# stm32f3-shield.net
KiCad netlist of a schematic drawn in EAGLE
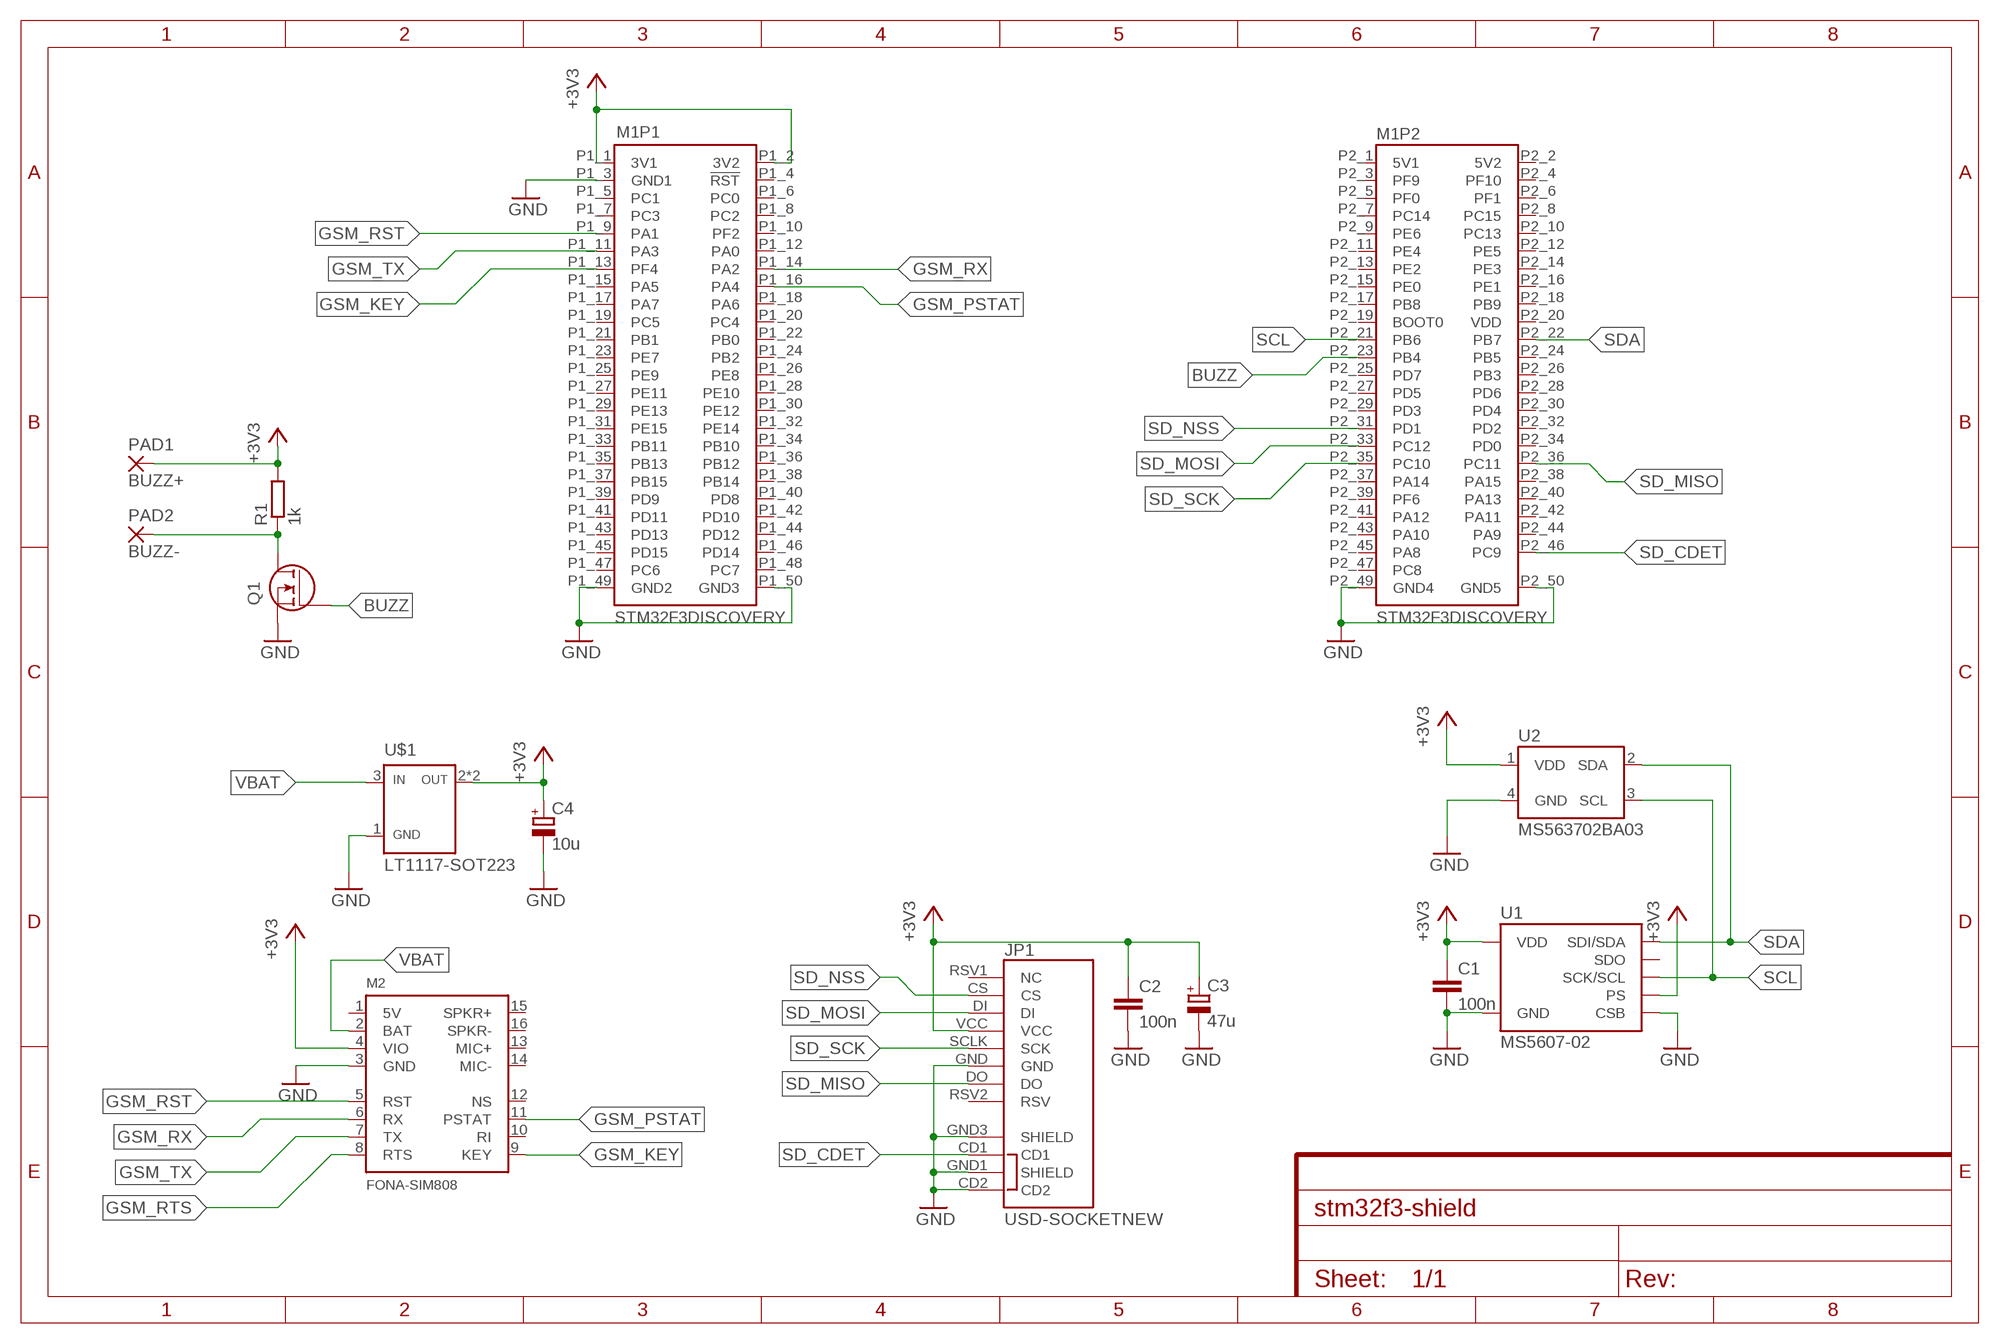
[diagram p0: schematic, sheet 1]

(export (version "E")
  (design (tool "Eeschema 10.0.6"))
  (components
    (comp (ref "C1")
      (value "100n")
      (footprint "eagle-import:C0805K")
      (libsource (lib "eagle-import") (part "C-EUC0805K"))
    )
    (comp (ref "C2")
      (value "100n")
      (footprint "eagle-import:C0805K")
      (libsource (lib "eagle-import") (part "C-EUC0805K"))
    )
    (comp (ref "C3")
      (value "47u")
      (footprint "eagle-import:SMC_B")
      (libsource (lib "eagle-import") (part "CPOL-EUSMCB"))
    )
    (comp (ref "C4")
      (value "10u")
      (footprint "eagle-import:SMC_B")
      (libsource (lib "eagle-import") (part "CPOL-EUSMCB"))
    )
    (comp (ref "JP1")
      (value "USD-SOCKETNEW")
      (footprint "eagle-import:MICRO-SD-SOCKET-PP")
      (libsource (lib "eagle-import") (part "USD-SOCKETNEW"))
    )
    (comp (ref "M1")
      (value "STM32F3DISCOVERY")
      (footprint "eagle-import:STM32F3DISCOVERY")
      (libsource (lib "eagle-import") (part "STM32F3DISCOVERY"))
    )
    (comp (ref "M2")
      (value "FONA-SIM808")
      (footprint "eagle-import:FONA-SIM808")
      (libsource (lib "eagle-import") (part "FONA-SIM808"))
    )
    (comp (ref "PAD1")
      (value "BUZZ+")
      (footprint "eagle-import:2,54_0,8")
      (libsource (lib "eagle-import") (part "2,54/0,8"))
    )
    (comp (ref "PAD2")
      (value "BUZZ-")
      (footprint "eagle-import:2,54_0,8")
      (libsource (lib "eagle-import") (part "2,54/0,8"))
    )
    (comp (ref "Q1")
      (value "MOSFET-N-SOT23-3")
      (footprint "eagle-import:SOT23-3")
      (libsource (lib "eagle-import") (part "MOSFET-N-SOT23-3"))
    )
    (comp (ref "R1")
      (value "1k")
      (footprint "eagle-import:R0603")
      (libsource (lib "eagle-import") (part "R-EU_R0603"))
    )
    (comp (ref "U$1")
      (value "LT1117-SOT223")
      (footprint "eagle-import:SOT223")
      (libsource (lib "eagle-import") (part "LT1117-SOT223"))
    )
    (comp (ref "U1")
      (value "MS5607-02")
      (footprint "eagle-import:LGA8")
      (libsource (lib "eagle-import") (part "MS5607-02"))
    )
    (comp (ref "U2")
      (value "MS563702BA03")
      (footprint "eagle-import:MS5637")
      (libsource (lib "eagle-import") (part "MS563702BA03"))
    )
  )
  (nets
    (net (code "1") (name "+3V3") (class "Default")
      (node (ref "C1") (pin "1") (pinfunction "1_1") (pintype "passive"))
      (node (ref "C2") (pin "1") (pinfunction "1_1") (pintype "passive"))
      (node (ref "C3") (pin "+") (pinfunction "+_+") (pintype "passive"))
      (node (ref "C4") (pin "+") (pinfunction "+_+") (pintype "passive"))
      (node (ref "JP1") (pin "VCC") (pinfunction "VCC_VCC") (pintype "bidirectional"))
      (node (ref "M1") (pin "P1_1") (pinfunction "3V1_P1_1") (pintype "bidirectional"))
      (node (ref "M1") (pin "P1_2") (pinfunction "3V2_P1_2") (pintype "bidirectional"))
      (node (ref "M2") (pin "4") (pinfunction "VIO_4") (pintype "bidirectional"))
      (node (ref "PAD1") (pin "1") (pinfunction "P_1") (pintype "passive"))
      (node (ref "R1") (pin "2") (pinfunction "2_2") (pintype "passive"))
      (node (ref "U$1") (pin "2") (pinfunction "OUT_2") (pintype "bidirectional"))
      (node (ref "U$1") (pin "4") (pinfunction "OUT_4") (pintype "bidirectional"))
      (node (ref "U1") (pin "1") (pinfunction "VDD_1") (pintype "power_in"))
      (node (ref "U1") (pin "2") (pinfunction "PS_2") (pintype "input"))
      (node (ref "U2") (pin "1") (pinfunction "VDD_1") (pintype "bidirectional"))
    )
    (net (code "2") (name "BUZZ") (class "Default")
      (node (ref "M1") (pin "P2_23") (pinfunction "PB4_P2_23") (pintype "bidirectional"))
      (node (ref "Q1") (pin "1") (pinfunction "G_1") (pintype "passive"))
    )
    (net (code "3") (name "GND") (class "Default")
      (node (ref "C1") (pin "2") (pinfunction "2_2") (pintype "passive"))
      (node (ref "C2") (pin "2") (pinfunction "2_2") (pintype "passive"))
      (node (ref "C3") (pin "-") (pinfunction "-_-") (pintype "passive"))
      (node (ref "C4") (pin "-") (pinfunction "-_-") (pintype "passive"))
      (node (ref "JP1") (pin "CD2") (pinfunction "CD2_CD2") (pintype "bidirectional"))
      (node (ref "JP1") (pin "GND") (pinfunction "GND_GND") (pintype "bidirectional"))
      (node (ref "JP1") (pin "GND1") (pinfunction "SHIELD_GND1") (pintype "bidirectional"))
      (node (ref "JP1") (pin "GND3") (pinfunction "SHIELD_GND3") (pintype "bidirectional"))
      (node (ref "M1") (pin "P1_3") (pinfunction "GND1_P1_3") (pintype "bidirectional"))
      (node (ref "M1") (pin "P1_49") (pinfunction "GND2_P1_49") (pintype "bidirectional"))
      (node (ref "M1") (pin "P1_50") (pinfunction "GND3_P1_50") (pintype "bidirectional"))
      (node (ref "M1") (pin "P2_49") (pinfunction "GND4_P2_49") (pintype "bidirectional"))
      (node (ref "M1") (pin "P2_50") (pinfunction "GND5_P2_50") (pintype "bidirectional"))
      (node (ref "M2") (pin "3") (pinfunction "GND_3") (pintype "bidirectional"))
      (node (ref "Q1") (pin "2") (pinfunction "S_2") (pintype "passive"))
      (node (ref "U$1") (pin "1") (pinfunction "GND_1") (pintype "bidirectional"))
      (node (ref "U1") (pin "3") (pinfunction "GND_3") (pintype "power_in"))
      (node (ref "U1") (pin "4") (pinfunction "CSB_4") (pintype "input"))
      (node (ref "U1") (pin "5") (pinfunction "CSB_5") (pintype "input"))
      (node (ref "U2") (pin "4") (pinfunction "GND_4") (pintype "bidirectional"))
    )
    (net (code "4") (name "GSM_KEY") (class "Default")
      (node (ref "M1") (pin "P1_13") (pinfunction "PF4_P1_13") (pintype "bidirectional"))
      (node (ref "M2") (pin "9") (pinfunction "KEY_9") (pintype "bidirectional"))
    )
    (net (code "5") (name "GSM_PSTAT") (class "Default")
      (node (ref "M1") (pin "P1_16") (pinfunction "PA4_P1_16") (pintype "bidirectional"))
      (node (ref "M2") (pin "11") (pinfunction "PSTAT_11") (pintype "bidirectional"))
    )
    (net (code "6") (name "GSM_RST") (class "Default")
      (node (ref "M1") (pin "P1_9") (pinfunction "PA1_P1_9") (pintype "bidirectional"))
      (node (ref "M2") (pin "5") (pinfunction "RST_5") (pintype "bidirectional"))
    )
    (net (code "7") (name "GSM_RTS") (class "Default")
      (node (ref "M2") (pin "8") (pinfunction "RTS_8") (pintype "bidirectional"))
    )
    (net (code "8") (name "GSM_RX") (class "Default")
      (node (ref "M1") (pin "P1_14") (pinfunction "PA2_P1_14") (pintype "bidirectional"))
      (node (ref "M2") (pin "6") (pinfunction "RX_6") (pintype "bidirectional"))
    )
    (net (code "9") (name "GSM_TX") (class "Default")
      (node (ref "M1") (pin "P1_11") (pinfunction "PA3_P1_11") (pintype "bidirectional"))
      (node (ref "M2") (pin "7") (pinfunction "TX_7") (pintype "bidirectional"))
    )
    (net (code "10") (name "Net-(PAD2-P)") (class "Default")
      (node (ref "PAD2") (pin "1") (pinfunction "P_1") (pintype "passive"))
      (node (ref "Q1") (pin "3") (pinfunction "D_3") (pintype "passive"))
      (node (ref "R1") (pin "1") (pinfunction "1_1") (pintype "passive"))
    )
    (net (code "11") (name "SCL") (class "Default")
      (node (ref "M1") (pin "P2_21") (pinfunction "PB6_P2_21") (pintype "bidirectional"))
      (node (ref "U1") (pin "8") (pinfunction "SCK/SCL_8") (pintype "input"))
      (node (ref "U2") (pin "3") (pinfunction "SCL_3") (pintype "bidirectional"))
    )
    (net (code "12") (name "SDA") (class "Default")
      (node (ref "M1") (pin "P2_22") (pinfunction "PB7_P2_22") (pintype "bidirectional"))
      (node (ref "U1") (pin "7") (pinfunction "SDI/SDA_7") (pintype "bidirectional"))
      (node (ref "U2") (pin "2") (pinfunction "SDA_2") (pintype "bidirectional"))
    )
    (net (code "13") (name "SD_CDET") (class "Default")
      (node (ref "JP1") (pin "CD1") (pinfunction "CD1_CD1") (pintype "bidirectional"))
      (node (ref "M1") (pin "P2_46") (pinfunction "PC9_P2_46") (pintype "bidirectional"))
    )
    (net (code "14") (name "SD_MISO") (class "Default")
      (node (ref "JP1") (pin "DO") (pinfunction "DO_DO") (pintype "bidirectional"))
      (node (ref "M1") (pin "P2_36") (pinfunction "PC11_P2_36") (pintype "bidirectional"))
    )
    (net (code "15") (name "SD_MOSI") (class "Default")
      (node (ref "JP1") (pin "DI") (pinfunction "DI_DI") (pintype "bidirectional"))
      (node (ref "M1") (pin "P2_33") (pinfunction "PC12_P2_33") (pintype "bidirectional"))
    )
    (net (code "16") (name "SD_NSS") (class "Default")
      (node (ref "JP1") (pin "CS") (pinfunction "CS_CS") (pintype "bidirectional"))
      (node (ref "M1") (pin "P2_31") (pinfunction "PD1_P2_31") (pintype "bidirectional"))
    )
    (net (code "17") (name "SD_SCK") (class "Default")
      (node (ref "JP1") (pin "SCLK") (pinfunction "SCK_SCLK") (pintype "bidirectional"))
      (node (ref "M1") (pin "P2_35") (pinfunction "PC10_P2_35") (pintype "bidirectional"))
    )
    (net (code "18") (name "VBAT") (class "Default")
      (node (ref "M2") (pin "2") (pinfunction "BAT_2") (pintype "bidirectional"))
      (node (ref "U$1") (pin "3") (pinfunction "IN_3") (pintype "bidirectional"))
    )
    (net (code "19") (name "unconnected-(JP1-NC-PadRSV1)") (class "Default")
      (node (ref "JP1") (pin "RSV1") (pinfunction "NC_RSV1") (pintype "bidirectional"))
    )
    (net (code "20") (name "unconnected-(JP1-RSV-PadRSV2)") (class "Default")
      (node (ref "JP1") (pin "RSV2") (pinfunction "RSV_RSV2") (pintype "bidirectional"))
    )
    (net (code "21") (name "unconnected-(M1A-PA0-PadP1_12)") (class "Default")
      (node (ref "M1") (pin "P1_12") (pinfunction "PA0_P1_12") (pintype "bidirectional"))
    )
    (net (code "22") (name "unconnected-(M1A-PA5-PadP1_15)") (class "Default")
      (node (ref "M1") (pin "P1_15") (pinfunction "PA5_P1_15") (pintype "bidirectional"))
    )
    (net (code "23") (name "unconnected-(M1A-PA6-PadP1_18)") (class "Default")
      (node (ref "M1") (pin "P1_18") (pinfunction "PA6_P1_18") (pintype "bidirectional"))
    )
    (net (code "24") (name "unconnected-(M1A-PA7-PadP1_17)") (class "Default")
      (node (ref "M1") (pin "P1_17") (pinfunction "PA7_P1_17") (pintype "bidirectional"))
    )
    (net (code "25") (name "unconnected-(M1A-PB0-PadP1_22)") (class "Default")
      (node (ref "M1") (pin "P1_22") (pinfunction "PB0_P1_22") (pintype "bidirectional"))
    )
    (net (code "26") (name "unconnected-(M1A-PB1-PadP1_21)") (class "Default")
      (node (ref "M1") (pin "P1_21") (pinfunction "PB1_P1_21") (pintype "bidirectional"))
    )
    (net (code "27") (name "unconnected-(M1A-PB2-PadP1_24)") (class "Default")
      (node (ref "M1") (pin "P1_24") (pinfunction "PB2_P1_24") (pintype "bidirectional"))
    )
    (net (code "28") (name "unconnected-(M1A-PB10-PadP1_34)") (class "Default")
      (node (ref "M1") (pin "P1_34") (pinfunction "PB10_P1_34") (pintype "bidirectional"))
    )
    (net (code "29") (name "unconnected-(M1A-PB11-PadP1_33)") (class "Default")
      (node (ref "M1") (pin "P1_33") (pinfunction "PB11_P1_33") (pintype "bidirectional"))
    )
    (net (code "30") (name "unconnected-(M1A-PB12-PadP1_36)") (class "Default")
      (node (ref "M1") (pin "P1_36") (pinfunction "PB12_P1_36") (pintype "bidirectional"))
    )
    (net (code "31") (name "unconnected-(M1A-PB13-PadP1_35)") (class "Default")
      (node (ref "M1") (pin "P1_35") (pinfunction "PB13_P1_35") (pintype "bidirectional"))
    )
    (net (code "32") (name "unconnected-(M1A-PB14-PadP1_38)") (class "Default")
      (node (ref "M1") (pin "P1_38") (pinfunction "PB14_P1_38") (pintype "bidirectional"))
    )
    (net (code "33") (name "unconnected-(M1A-PB15-PadP1_37)") (class "Default")
      (node (ref "M1") (pin "P1_37") (pinfunction "PB15_P1_37") (pintype "bidirectional"))
    )
    (net (code "34") (name "unconnected-(M1A-PC0-PadP1_6)") (class "Default")
      (node (ref "M1") (pin "P1_6") (pinfunction "PC0_P1_6") (pintype "bidirectional"))
    )
    (net (code "35") (name "unconnected-(M1A-PC1-PadP1_5)") (class "Default")
      (node (ref "M1") (pin "P1_5") (pinfunction "PC1_P1_5") (pintype "bidirectional"))
    )
    (net (code "36") (name "unconnected-(M1A-PC2-PadP1_8)") (class "Default")
      (node (ref "M1") (pin "P1_8") (pinfunction "PC2_P1_8") (pintype "bidirectional"))
    )
    (net (code "37") (name "unconnected-(M1A-PC3-PadP1_7)") (class "Default")
      (node (ref "M1") (pin "P1_7") (pinfunction "PC3_P1_7") (pintype "bidirectional"))
    )
    (net (code "38") (name "unconnected-(M1A-PC4-PadP1_20)") (class "Default")
      (node (ref "M1") (pin "P1_20") (pinfunction "PC4_P1_20") (pintype "bidirectional"))
    )
    (net (code "39") (name "unconnected-(M1A-PC5-PadP1_19)") (class "Default")
      (node (ref "M1") (pin "P1_19") (pinfunction "PC5_P1_19") (pintype "bidirectional"))
    )
    (net (code "40") (name "unconnected-(M1A-PC6-PadP1_47)") (class "Default")
      (node (ref "M1") (pin "P1_47") (pinfunction "PC6_P1_47") (pintype "bidirectional"))
    )
    (net (code "41") (name "unconnected-(M1A-PC7-PadP1_48)") (class "Default")
      (node (ref "M1") (pin "P1_48") (pinfunction "PC7_P1_48") (pintype "bidirectional"))
    )
    (net (code "42") (name "unconnected-(M1A-PD8-PadP1_40)") (class "Default")
      (node (ref "M1") (pin "P1_40") (pinfunction "PD8_P1_40") (pintype "bidirectional"))
    )
    (net (code "43") (name "unconnected-(M1A-PD9-PadP1_39)") (class "Default")
      (node (ref "M1") (pin "P1_39") (pinfunction "PD9_P1_39") (pintype "bidirectional"))
    )
    (net (code "44") (name "unconnected-(M1A-PD10-PadP1_42)") (class "Default")
      (node (ref "M1") (pin "P1_42") (pinfunction "PD10_P1_42") (pintype "bidirectional"))
    )
    (net (code "45") (name "unconnected-(M1A-PD11-PadP1_41)") (class "Default")
      (node (ref "M1") (pin "P1_41") (pinfunction "PD11_P1_41") (pintype "bidirectional"))
    )
    (net (code "46") (name "unconnected-(M1A-PD12-PadP1_44)") (class "Default")
      (node (ref "M1") (pin "P1_44") (pinfunction "PD12_P1_44") (pintype "bidirectional"))
    )
    (net (code "47") (name "unconnected-(M1A-PD13-PadP1_43)") (class "Default")
      (node (ref "M1") (pin "P1_43") (pinfunction "PD13_P1_43") (pintype "bidirectional"))
    )
    (net (code "48") (name "unconnected-(M1A-PD14-PadP1_46)") (class "Default")
      (node (ref "M1") (pin "P1_46") (pinfunction "PD14_P1_46") (pintype "bidirectional"))
    )
    (net (code "49") (name "unconnected-(M1A-PD15-PadP1_45)") (class "Default")
      (node (ref "M1") (pin "P1_45") (pinfunction "PD15_P1_45") (pintype "bidirectional"))
    )
    (net (code "50") (name "unconnected-(M1A-PE7-PadP1_23)") (class "Default")
      (node (ref "M1") (pin "P1_23") (pinfunction "PE7_P1_23") (pintype "bidirectional"))
    )
    (net (code "51") (name "unconnected-(M1A-PE8-PadP1_26)") (class "Default")
      (node (ref "M1") (pin "P1_26") (pinfunction "PE8_P1_26") (pintype "bidirectional"))
    )
    (net (code "52") (name "unconnected-(M1A-PE9-PadP1_25)") (class "Default")
      (node (ref "M1") (pin "P1_25") (pinfunction "PE9_P1_25") (pintype "bidirectional"))
    )
    (net (code "53") (name "unconnected-(M1A-PE10-PadP1_28)") (class "Default")
      (node (ref "M1") (pin "P1_28") (pinfunction "PE10_P1_28") (pintype "bidirectional"))
    )
    (net (code "54") (name "unconnected-(M1A-PE11-PadP1_27)") (class "Default")
      (node (ref "M1") (pin "P1_27") (pinfunction "PE11_P1_27") (pintype "bidirectional"))
    )
    (net (code "55") (name "unconnected-(M1A-PE12-PadP1_30)") (class "Default")
      (node (ref "M1") (pin "P1_30") (pinfunction "PE12_P1_30") (pintype "bidirectional"))
    )
    (net (code "56") (name "unconnected-(M1A-PE13-PadP1_29)") (class "Default")
      (node (ref "M1") (pin "P1_29") (pinfunction "PE13_P1_29") (pintype "bidirectional"))
    )
    (net (code "57") (name "unconnected-(M1A-PE14-PadP1_32)") (class "Default")
      (node (ref "M1") (pin "P1_32") (pinfunction "PE14_P1_32") (pintype "bidirectional"))
    )
    (net (code "58") (name "unconnected-(M1A-PE15-PadP1_31)") (class "Default")
      (node (ref "M1") (pin "P1_31") (pinfunction "PE15_P1_31") (pintype "bidirectional"))
    )
    (net (code "59") (name "unconnected-(M1A-PF2-PadP1_10)") (class "Default")
      (node (ref "M1") (pin "P1_10") (pinfunction "PF2_P1_10") (pintype "bidirectional"))
    )
    (net (code "60") (name "unconnected-(M1A-~{RST}-PadP1_4)") (class "Default")
      (node (ref "M1") (pin "P1_4") (pinfunction "~{RST}_P1_4") (pintype "bidirectional"))
    )
    (net (code "61") (name "unconnected-(M1B-5V1-PadP2_1)") (class "Default")
      (node (ref "M1") (pin "P2_1") (pinfunction "5V1_P2_1") (pintype "bidirectional"))
    )
    (net (code "62") (name "unconnected-(M1B-5V2-PadP2_2)") (class "Default")
      (node (ref "M1") (pin "P2_2") (pinfunction "5V2_P2_2") (pintype "bidirectional"))
    )
    (net (code "63") (name "unconnected-(M1B-BOOT0-PadP2_19)") (class "Default")
      (node (ref "M1") (pin "P2_19") (pinfunction "BOOT0_P2_19") (pintype "bidirectional"))
    )
    (net (code "64") (name "unconnected-(M1B-PA8-PadP2_45)") (class "Default")
      (node (ref "M1") (pin "P2_45") (pinfunction "PA8_P2_45") (pintype "bidirectional"))
    )
    (net (code "65") (name "unconnected-(M1B-PA9-PadP2_44)") (class "Default")
      (node (ref "M1") (pin "P2_44") (pinfunction "PA9_P2_44") (pintype "bidirectional"))
    )
    (net (code "66") (name "unconnected-(M1B-PA10-PadP2_43)") (class "Default")
      (node (ref "M1") (pin "P2_43") (pinfunction "PA10_P2_43") (pintype "bidirectional"))
    )
    (net (code "67") (name "unconnected-(M1B-PA11-PadP2_42)") (class "Default")
      (node (ref "M1") (pin "P2_42") (pinfunction "PA11_P2_42") (pintype "bidirectional"))
    )
    (net (code "68") (name "unconnected-(M1B-PA12-PadP2_41)") (class "Default")
      (node (ref "M1") (pin "P2_41") (pinfunction "PA12_P2_41") (pintype "bidirectional"))
    )
    (net (code "69") (name "unconnected-(M1B-PA13-PadP2_40)") (class "Default")
      (node (ref "M1") (pin "P2_40") (pinfunction "PA13_P2_40") (pintype "bidirectional"))
    )
    (net (code "70") (name "unconnected-(M1B-PA14-PadP2_37)") (class "Default")
      (node (ref "M1") (pin "P2_37") (pinfunction "PA14_P2_37") (pintype "bidirectional"))
    )
    (net (code "71") (name "unconnected-(M1B-PA15-PadP2_38)") (class "Default")
      (node (ref "M1") (pin "P2_38") (pinfunction "PA15_P2_38") (pintype "bidirectional"))
    )
    (net (code "72") (name "unconnected-(M1B-PB3-PadP2_26)") (class "Default")
      (node (ref "M1") (pin "P2_26") (pinfunction "PB3_P2_26") (pintype "bidirectional"))
    )
    (net (code "73") (name "unconnected-(M1B-PB5-PadP2_24)") (class "Default")
      (node (ref "M1") (pin "P2_24") (pinfunction "PB5_P2_24") (pintype "bidirectional"))
    )
    (net (code "74") (name "unconnected-(M1B-PB8-PadP2_17)") (class "Default")
      (node (ref "M1") (pin "P2_17") (pinfunction "PB8_P2_17") (pintype "bidirectional"))
    )
    (net (code "75") (name "unconnected-(M1B-PB9-PadP2_18)") (class "Default")
      (node (ref "M1") (pin "P2_18") (pinfunction "PB9_P2_18") (pintype "bidirectional"))
    )
    (net (code "76") (name "unconnected-(M1B-PC8-PadP2_47)") (class "Default")
      (node (ref "M1") (pin "P2_47") (pinfunction "PC8_P2_47") (pintype "bidirectional"))
    )
    (net (code "77") (name "unconnected-(M1B-PC13-PadP2_10)") (class "Default")
      (node (ref "M1") (pin "P2_10") (pinfunction "PC13_P2_10") (pintype "bidirectional"))
    )
    (net (code "78") (name "unconnected-(M1B-PC14-PadP2_7)") (class "Default")
      (node (ref "M1") (pin "P2_7") (pinfunction "PC14_P2_7") (pintype "bidirectional"))
    )
    (net (code "79") (name "unconnected-(M1B-PC15-PadP2_8)") (class "Default")
      (node (ref "M1") (pin "P2_8") (pinfunction "PC15_P2_8") (pintype "bidirectional"))
    )
    (net (code "80") (name "unconnected-(M1B-PD0-PadP2_34)") (class "Default")
      (node (ref "M1") (pin "P2_34") (pinfunction "PD0_P2_34") (pintype "bidirectional"))
    )
    (net (code "81") (name "unconnected-(M1B-PD2-PadP2_32)") (class "Default")
      (node (ref "M1") (pin "P2_32") (pinfunction "PD2_P2_32") (pintype "bidirectional"))
    )
    (net (code "82") (name "unconnected-(M1B-PD3-PadP2_29)") (class "Default")
      (node (ref "M1") (pin "P2_29") (pinfunction "PD3_P2_29") (pintype "bidirectional"))
    )
    (net (code "83") (name "unconnected-(M1B-PD4-PadP2_30)") (class "Default")
      (node (ref "M1") (pin "P2_30") (pinfunction "PD4_P2_30") (pintype "bidirectional"))
    )
    (net (code "84") (name "unconnected-(M1B-PD5-PadP2_27)") (class "Default")
      (node (ref "M1") (pin "P2_27") (pinfunction "PD5_P2_27") (pintype "bidirectional"))
    )
    (net (code "85") (name "unconnected-(M1B-PD6-PadP2_28)") (class "Default")
      (node (ref "M1") (pin "P2_28") (pinfunction "PD6_P2_28") (pintype "bidirectional"))
    )
    (net (code "86") (name "unconnected-(M1B-PD7-PadP2_25)") (class "Default")
      (node (ref "M1") (pin "P2_25") (pinfunction "PD7_P2_25") (pintype "bidirectional"))
    )
    (net (code "87") (name "unconnected-(M1B-PE0-PadP2_15)") (class "Default")
      (node (ref "M1") (pin "P2_15") (pinfunction "PE0_P2_15") (pintype "bidirectional"))
    )
    (net (code "88") (name "unconnected-(M1B-PE1-PadP2_16)") (class "Default")
      (node (ref "M1") (pin "P2_16") (pinfunction "PE1_P2_16") (pintype "bidirectional"))
    )
    (net (code "89") (name "unconnected-(M1B-PE2-PadP2_13)") (class "Default")
      (node (ref "M1") (pin "P2_13") (pinfunction "PE2_P2_13") (pintype "bidirectional"))
    )
    (net (code "90") (name "unconnected-(M1B-PE3-PadP2_14)") (class "Default")
      (node (ref "M1") (pin "P2_14") (pinfunction "PE3_P2_14") (pintype "bidirectional"))
    )
    (net (code "91") (name "unconnected-(M1B-PE4-PadP2_11)") (class "Default")
      (node (ref "M1") (pin "P2_11") (pinfunction "PE4_P2_11") (pintype "bidirectional"))
    )
    (net (code "92") (name "unconnected-(M1B-PE5-PadP2_12)") (class "Default")
      (node (ref "M1") (pin "P2_12") (pinfunction "PE5_P2_12") (pintype "bidirectional"))
    )
    (net (code "93") (name "unconnected-(M1B-PE6-PadP2_9)") (class "Default")
      (node (ref "M1") (pin "P2_9") (pinfunction "PE6_P2_9") (pintype "bidirectional"))
    )
    (net (code "94") (name "unconnected-(M1B-PF0-PadP2_5)") (class "Default")
      (node (ref "M1") (pin "P2_5") (pinfunction "PF0_P2_5") (pintype "bidirectional"))
    )
    (net (code "95") (name "unconnected-(M1B-PF1-PadP2_6)") (class "Default")
      (node (ref "M1") (pin "P2_6") (pinfunction "PF1_P2_6") (pintype "bidirectional"))
    )
    (net (code "96") (name "unconnected-(M1B-PF6-PadP2_39)") (class "Default")
      (node (ref "M1") (pin "P2_39") (pinfunction "PF6_P2_39") (pintype "bidirectional"))
    )
    (net (code "97") (name "unconnected-(M1B-PF9-PadP2_3)") (class "Default")
      (node (ref "M1") (pin "P2_3") (pinfunction "PF9_P2_3") (pintype "bidirectional"))
    )
    (net (code "98") (name "unconnected-(M1B-PF10-PadP2_4)") (class "Default")
      (node (ref "M1") (pin "P2_4") (pinfunction "PF10_P2_4") (pintype "bidirectional"))
    )
    (net (code "99") (name "unconnected-(M1B-VDD-PadP2_20)") (class "Default")
      (node (ref "M1") (pin "P2_20") (pinfunction "VDD_P2_20") (pintype "bidirectional"))
    )
    (net (code "100") (name "unconnected-(M2-5V-Pad1)") (class "Default")
      (node (ref "M2") (pin "1") (pinfunction "5V_1") (pintype "bidirectional"))
    )
    (net (code "101") (name "unconnected-(M2-MIC+-Pad13)") (class "Default")
      (node (ref "M2") (pin "13") (pinfunction "MIC+_13") (pintype "bidirectional"))
    )
    (net (code "102") (name "unconnected-(M2-MIC--Pad14)") (class "Default")
      (node (ref "M2") (pin "14") (pinfunction "MIC-_14") (pintype "bidirectional"))
    )
    (net (code "103") (name "unconnected-(M2-NS-Pad12)") (class "Default")
      (node (ref "M2") (pin "12") (pinfunction "NS_12") (pintype "bidirectional"))
    )
    (net (code "104") (name "unconnected-(M2-RI-Pad10)") (class "Default")
      (node (ref "M2") (pin "10") (pinfunction "RI_10") (pintype "bidirectional"))
    )
    (net (code "105") (name "unconnected-(M2-SPKR+-Pad15)") (class "Default")
      (node (ref "M2") (pin "15") (pinfunction "SPKR+_15") (pintype "bidirectional"))
    )
    (net (code "106") (name "unconnected-(M2-SPKR--Pad16)") (class "Default")
      (node (ref "M2") (pin "16") (pinfunction "SPKR-_16") (pintype "bidirectional"))
    )
    (net (code "107") (name "unconnected-(U1-SDO-Pad6)") (class "Default")
      (node (ref "U1") (pin "6") (pinfunction "SDO_6") (pintype "bidirectional"))
    )
  )
)
